# Schematic.net
KiCad netlist of a schematic drawn in Altium Designer
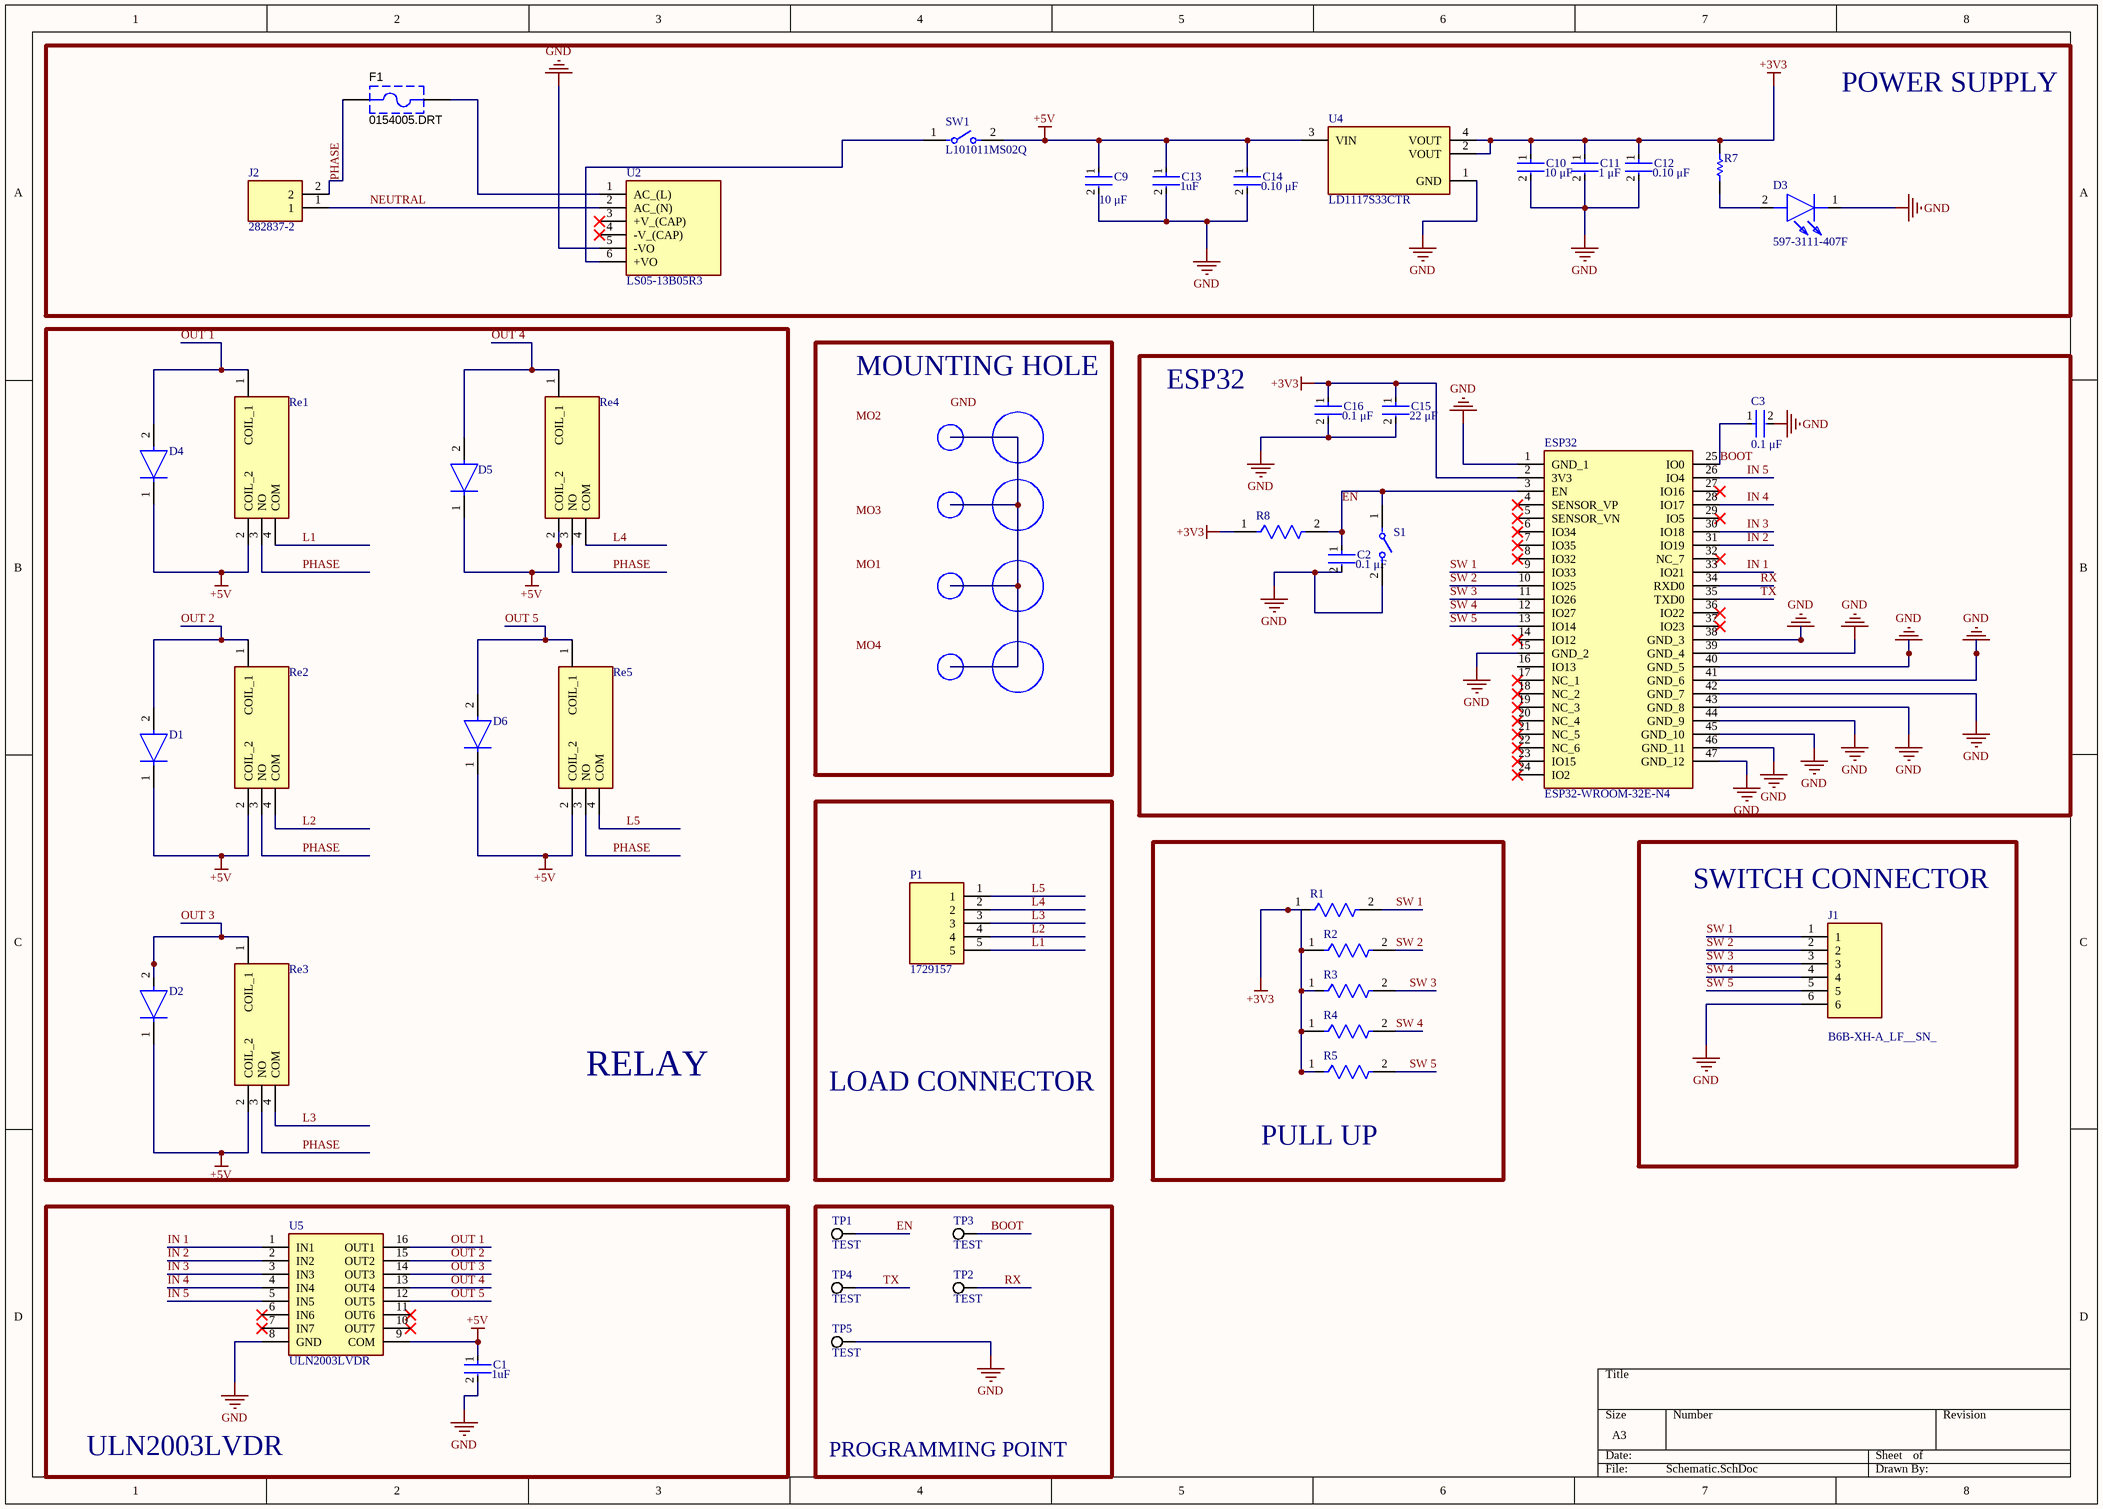
[diagram p0: Schematic.SchDoc]

(export (version "E")
  (design (tool "Eeschema 10.0.6"))
  (components
    (comp (ref "C1")
      (value "C0402C104K8PACTU")
      (footprint "FP-C0402-BB-MFG")
      (description "CAP CER 0.1UF 10V X5R 0402")
      (fields
        (field (name "CAPACITANCE") "1uF")
        (field (name "MANUFACTURER") "Kemet")
        (field (name "TOLERANCE") "0.1")
      )
      (libsource (lib "Altium Content Vault") (part "b4654b650e69147ec39a6b967a45e02"))
    )
    (comp (ref "C2")
      (value "0.1 μF")
      (footprint "FP-C0402-BB-MFG")
      (description "CAP CER 0.1UF 10V X5R 0402")
      (fields (field (name "MANUFACTURER") "Kemet") (field (name "TOLERANCE") "0.1"))
      (libsource (lib "Altium Content Vault") (part "b4654b650e69147ec39a6b967a45e02"))
    )
    (comp (ref "C3")
      (value "0.1 μF")
      (footprint "FP-C0402-BB-MFG")
      (description "CAP CER 0.1UF 10V X5R 0402")
      (fields (field (name "MANUFACTURER") "Kemet") (field (name "TOLERANCE") "0.1"))
      (libsource (lib "Altium Content Vault") (part "b4654b650e69147ec39a6b967a45e02"))
    )
    (comp (ref "C9")
      (value "10 μF")
      (footprint "FP-C0402-BB-MFG")
      (description "CAP CER 0.1UF 10V X5R 0402")
      (fields (field (name "MANUFACTURER") "Kemet") (field (name "TOLERANCE") "0.1"))
      (libsource (lib "Altium Content Vault") (part "b4654b650e69147ec39a6b967a45e02"))
    )
    (comp (ref "C10")
      (value "10 μF")
      (footprint "FP-C0402-BB-MFG")
      (description "CAP CER 0.1UF 10V X5R 0402")
      (fields (field (name "MANUFACTURER") "Kemet") (field (name "TOLERANCE") "0.1"))
      (libsource (lib "Altium Content Vault") (part "b4654b650e69147ec39a6b967a45e02"))
    )
    (comp (ref "C11")
      (value "1 μF")
      (footprint "FP-C0402-BB-MFG")
      (description "CAP CER 0.1UF 10V X5R 0402")
      (fields (field (name "MANUFACTURER") "Kemet") (field (name "TOLERANCE") "0.1"))
      (libsource (lib "Altium Content Vault") (part "b4654b650e69147ec39a6b967a45e02"))
    )
    (comp (ref "C12")
      (value "C0402C104K8PACTU")
      (footprint "FP-C0402-BB-MFG")
      (description "CAP CER 0.1UF 10V X5R 0402")
      (fields
        (field (name "CAPACITANCE") "0.10 μF")
        (field (name "MANUFACTURER") "Kemet")
        (field (name "TOLERANCE") "0.1")
      )
      (libsource (lib "Altium Content Vault") (part "b4654b650e69147ec39a6b967a45e02"))
    )
    (comp (ref "C13")
      (value "C0402C104K8PACTU")
      (footprint "FP-C0402-BB-MFG")
      (description "CAP CER 0.1UF 10V X5R 0402")
      (fields
        (field (name "CAPACITANCE") "1uF")
        (field (name "MANUFACTURER") "Kemet")
        (field (name "TOLERANCE") "0.1")
      )
      (libsource (lib "Altium Content Vault") (part "b4654b650e69147ec39a6b967a45e02"))
    )
    (comp (ref "C14")
      (value "0.10 μF")
      (footprint "FP-C0402-BB-MFG")
      (description "CAP CER 0.1UF 10V X5R 0402")
      (fields (field (name "MANUFACTURER") "Kemet") (field (name "TOLERANCE") "0.1"))
      (libsource (lib "Altium Content Vault") (part "b4654b650e69147ec39a6b967a45e02"))
    )
    (comp (ref "C15")
      (value "22 μF")
      (footprint "FP-C0402-BB-MFG")
      (description "CAP CER 0.1UF 10V X5R 0402")
      (fields (field (name "MANUFACTURER") "Kemet") (field (name "TOLERANCE") "0.1"))
      (libsource (lib "Altium Content Vault") (part "b4654b650e69147ec39a6b967a45e02"))
    )
    (comp (ref "C16")
      (value "0.1 μF")
      (footprint "FP-C0402-BB-MFG")
      (description "CAP CER 0.1UF 10V X5R 0402")
      (fields (field (name "MANUFACTURER") "Kemet") (field (name "TOLERANCE") "0.1"))
      (libsource (lib "Altium Content Vault") (part "b4654b650e69147ec39a6b967a45e02"))
    )
    (comp (ref "D1")
      (value "1N4148")
      (footprint "FP-017AG-MFG")
      (description "DIODE GEN PURP 100V 200MA DO35")
      (fields (field (name "VOLTAGE") "100V"))
      (libsource (lib "Altium Content Vault") (part "d7152d700b627762746794eb795d46e"))
    )
    (comp (ref "D2")
      (value "1N4148")
      (footprint "FP-017AG-MFG")
      (description "DIODE GEN PURP 100V 200MA DO35")
      (fields (field (name "VOLTAGE") "100V"))
      (libsource (lib "Altium Content Vault") (part "d7152d700b627762746794eb795d46e"))
    )
    (comp (ref "D3")
      (value "597-3111-407F")
      (footprint "SamacSys:LEDC3015X150N")
      (description "LED")
      (fields (field (name "MOUSER PART NUMBER") "645-597-3111-407F"))
      (libsource (lib "*") (part "597-3111-407F"))
    )
    (comp (ref "D4")
      (value "1N4148")
      (footprint "FP-017AG-MFG")
      (description "DIODE GEN PURP 100V 200MA DO35")
      (fields (field (name "VOLTAGE") "100V"))
      (libsource (lib "Altium Content Vault") (part "d7152d700b627762746794eb795d46e"))
    )
    (comp (ref "D5")
      (value "1N4148")
      (footprint "FP-017AG-MFG")
      (description "DIODE GEN PURP 100V 200MA DO35")
      (fields (field (name "VOLTAGE") "100V"))
      (libsource (lib "Altium Content Vault") (part "d7152d700b627762746794eb795d46e"))
    )
    (comp (ref "D6")
      (value "1N4148")
      (footprint "FP-017AG-MFG")
      (description "DIODE GEN PURP 100V 200MA DO35")
      (fields (field (name "VOLTAGE") "100V"))
      (libsource (lib "Altium Content Vault") (part "d7152d700b627762746794eb795d46e"))
    )
    (comp (ref "ESP32")
      (value "ESP32-WROOM-32E-N4")
      (footprint "SamacSys:ESP32WROOM32EN4")
      (description "Integrated Circuit")
      (fields (field (name "MOUSER PART NUMBER") "356-ESP32WRM32E132PH"))
      (libsource (lib "*") (part "ESP32-WROOM-32E-N4"))
    )
    (comp (ref "F1")
      (value "0154005.DRT")
      (footprint "LFUS-154_V")
      (description "Fuse and Holder Combination, 125 V, 5 A, -55 to 125 degC, 2-Pin SMD, RoHS, Tape and Reel")
      (fields (field (name "MANUFACTURER") "Littelfuse"))
      (libsource (lib "Altium Content Vault") (part "FUSE_HOLDER-2"))
    )
    (comp (ref "J1")
      (value "B6B-XH-A_LF__SN_")
      (footprint "SamacSys:SHDR6W64P0X250_1X6_1740X575X700P")
      (description "Connector")
      (fields
        (field (name "MANUFACTURER_PART_NUMBER") "B6B-XH-A(LF)(SN)")
        (field (name "MOUSER PART NUMBER") "306-B6BXHALFSN")
      )
      (libsource (lib "*") (part "B6B-XH-A_LF__SN_"))
    )
    (comp (ref "J2")
      (value "282837-2")
      (footprint "SamacSys:2828372")
      (description "Connector")
      (fields (field (name "MOUSER PART NUMBER") "571-2828372"))
      (libsource (lib "*") (part "282837-2"))
    )
    (comp (ref "P1")
      (value "1729157")
      (footprint "SamacSys:1729157")
      (description "Connector")
      (fields (field (name "MOUSER PART NUMBER") "651-1729157"))
      (libsource (lib "*") (part "1729157"))
    )
    (comp (ref "R1")
      (value "CRCW040210K0JNED")
      (footprint "FP-CRCW0402-e3-IPC_B")
      (description "RES Thick Film, 10kΩ, 5%, 0.063W, 200ppm/°C, 0402")
      (fields (field (name "TOLERANCE") "5%"))
      (libsource (lib "Altium Content Vault") (part "1029c3af85768c4190bb7ad29bc67b5"))
    )
    (comp (ref "R2")
      (value "CRCW040210K0JNED")
      (footprint "FP-CRCW0402-e3-IPC_B")
      (description "RES Thick Film, 10kΩ, 5%, 0.063W, 200ppm/°C, 0402")
      (fields (field (name "TOLERANCE") "5%"))
      (libsource (lib "Altium Content Vault") (part "1029c3af85768c4190bb7ad29bc67b5"))
    )
    (comp (ref "R3")
      (value "CRCW040210K0JNED")
      (footprint "FP-CRCW0402-e3-IPC_B")
      (description "RES Thick Film, 10kΩ, 5%, 0.063W, 200ppm/°C, 0402")
      (fields (field (name "TOLERANCE") "5%"))
      (libsource (lib "Altium Content Vault") (part "1029c3af85768c4190bb7ad29bc67b5"))
    )
    (comp (ref "R4")
      (value "CRCW040210K0JNED")
      (footprint "FP-CRCW0402-e3-IPC_B")
      (description "RES Thick Film, 10kΩ, 5%, 0.063W, 200ppm/°C, 0402")
      (fields (field (name "TOLERANCE") "5%"))
      (libsource (lib "Altium Content Vault") (part "1029c3af85768c4190bb7ad29bc67b5"))
    )
    (comp (ref "R5")
      (value "CRCW040210K0JNED")
      (footprint "FP-CRCW0402-e3-IPC_B")
      (description "RES Thick Film, 10kΩ, 5%, 0.063W, 200ppm/°C, 0402")
      (fields (field (name "TOLERANCE") "5%"))
      (libsource (lib "Altium Content Vault") (part "1029c3af85768c4190bb7ad29bc67b5"))
    )
    (comp (ref "R7")
      (value "ERJ-3EKF3300V")
      (footprint "RESC1608X55X30LL15T15")
      (description "Chip Resistor, 330 Ohm, +/- 1%, 0.1 W, -55 to 155 degC, 0603 (1608 Metric), RoHS, Tape and Reel")
      (libsource (lib "Altium Content Vault") (part "RES-2"))
    )
    (comp (ref "R8")
      (value "CRCW040210K0JNED")
      (footprint "FP-CRCW0402-e3-IPC_B")
      (description "RES Thick Film, 10kΩ, 5%, 0.063W, 200ppm/°C, 0402")
      (fields (field (name "TOLERANCE") "5%"))
      (libsource (lib "Altium Content Vault") (part "1029c3af85768c4190bb7ad29bc67b5"))
    )
    (comp (ref "Re1")
      (value "HF46F-G_5-HS1T")
      (footprint "SamacSys:HF46FG5HS1T")
      (description "Relay or Contactor")
      (fields (field (name "MANUFACTURER_PART_NUMBER") "HF46F-G/5-HS1T"))
      (libsource (lib "*") (part "HF46F-G_5-HS1T"))
    )
    (comp (ref "Re2")
      (value "HF46F-G_5-HS1T")
      (footprint "SamacSys:HF46FG5HS1T")
      (description "Relay or Contactor")
      (fields (field (name "MANUFACTURER_PART_NUMBER") "HF46F-G/5-HS1T"))
      (libsource (lib "*") (part "HF46F-G_5-HS1T"))
    )
    (comp (ref "Re3")
      (value "HF46F-G_5-HS1T")
      (footprint "SamacSys:HF46FG5HS1T")
      (description "Relay or Contactor")
      (fields (field (name "MANUFACTURER_PART_NUMBER") "HF46F-G/5-HS1T"))
      (libsource (lib "*") (part "HF46F-G_5-HS1T"))
    )
    (comp (ref "Re4")
      (value "HF46F-G_5-HS1T")
      (footprint "SamacSys:HF46FG5HS1T")
      (description "Relay or Contactor")
      (fields (field (name "MANUFACTURER_PART_NUMBER") "HF46F-G/5-HS1T"))
      (libsource (lib "*") (part "HF46F-G_5-HS1T"))
    )
    (comp (ref "Re5")
      (value "HF46F-G_5-HS1T")
      (footprint "SamacSys:HF46FG5HS1T")
      (description "Relay or Contactor")
      (fields (field (name "MANUFACTURER_PART_NUMBER") "HF46F-G/5-HS1T"))
      (libsource (lib "*") (part "HF46F-G_5-HS1T"))
    )
    (comp (ref "S1")
      (value "L101011MS02Q")
      (footprint "FP-L101011MS02Q-MFG")
      (description "SWITCH SLIDE SPST 4A 125V")
      (libsource (lib "Altium Content Vault") (part "bb27bde45df87f1f469753f287ef5ae"))
    )
    (comp (ref "SW1")
      (value "L101011MS02Q")
      (footprint "FP-L101011MS02Q-MFG")
      (description "SWITCH SLIDE SPST 4A 125V")
      (libsource (lib "Altium Content Vault") (part "bb27bde45df87f1f469753f287ef5ae"))
    )
    (comp (ref "TP1")
      (value "TEST")
      (footprint "KSTN-5012_V")
      (description "Test Point, White, Through Hole, RoHS, Bulk")
      (fields (field (name "MANUFACTURER") "Keystone"))
      (libsource (lib "Altium Content Vault") (part "TESTPOINT_WHITE"))
    )
    (comp (ref "TP2")
      (value "TEST")
      (footprint "KSTN-5012_V")
      (description "Test Point, White, Through Hole, RoHS, Bulk")
      (fields (field (name "MANUFACTURER") "Keystone"))
      (libsource (lib "Altium Content Vault") (part "TESTPOINT_WHITE"))
    )
    (comp (ref "TP3")
      (value "TEST")
      (footprint "KSTN-5012_V")
      (description "Test Point, White, Through Hole, RoHS, Bulk")
      (fields (field (name "MANUFACTURER") "Keystone"))
      (libsource (lib "Altium Content Vault") (part "TESTPOINT_WHITE"))
    )
    (comp (ref "TP4")
      (value "TEST")
      (footprint "KSTN-5012_V")
      (description "Test Point, White, Through Hole, RoHS, Bulk")
      (fields (field (name "MANUFACTURER") "Keystone"))
      (libsource (lib "Altium Content Vault") (part "TESTPOINT_WHITE"))
    )
    (comp (ref "TP5")
      (value "TEST")
      (footprint "KSTN-5012_V")
      (description "Test Point, White, Through Hole, RoHS, Bulk")
      (fields (field (name "MANUFACTURER") "Keystone"))
      (libsource (lib "Altium Content Vault") (part "TESTPOINT_WHITE"))
    )
    (comp (ref "U2")
      (value "LS05-13B05R3")
      (footprint "SamacSys:LS0513B05R3")
      (description "Power Supply")
      (libsource (lib "*") (part "LS05-13B05R3"))
    )
    (comp (ref "U4")
      (value "LD1117S33CTR")
      (footprint "FP-SOT-223-0046067_14-MFG")
      (description "IC REG LINEAR 3.3V 800MA SOT223")
      (libsource (lib "Altium Content Vault") (part "7818869c5c16ceab15634627166a29d"))
    )
    (comp (ref "U5")
      (value "ULN2003LVDR")
      (footprint "SamacSys:SOIC127P600X175-16N")
      (description "Integrated Circuit")
      (fields (field (name "MOUSER PART NUMBER") "595-ULN2003LVDR"))
      (libsource (lib "*") (part "ULN2003LVDR"))
    )
  )
  (nets
    (net (code "1") (name "+3V3") (class "Default")
      (node (ref "C10") (pin "1") (pinfunction "1_1") (pintype "passive"))
      (node (ref "C11") (pin "1") (pinfunction "1_1") (pintype "passive"))
      (node (ref "C12") (pin "1") (pinfunction "1_1") (pintype "passive"))
      (node (ref "C15") (pin "1") (pinfunction "1_1") (pintype "passive"))
      (node (ref "C16") (pin "1") (pinfunction "1_1") (pintype "passive"))
      (node (ref "ESP32") (pin "2") (pinfunction "3V3_2") (pintype "passive"))
      (node (ref "R1") (pin "1") (pinfunction "1_1") (pintype "passive"))
      (node (ref "R2") (pin "1") (pinfunction "1_1") (pintype "passive"))
      (node (ref "R3") (pin "1") (pinfunction "1_1") (pintype "passive"))
      (node (ref "R4") (pin "1") (pinfunction "1_1") (pintype "passive"))
      (node (ref "R5") (pin "1") (pinfunction "1_1") (pintype "passive"))
      (node (ref "R7") (pin "2") (pinfunction "2_2") (pintype "passive"))
      (node (ref "R8") (pin "1") (pinfunction "1_1") (pintype "passive"))
      (node (ref "U4") (pin "2") (pinfunction "VOUT_2") (pintype "power_in"))
      (node (ref "U4") (pin "4") (pinfunction "VOUT_4") (pintype "power_in"))
    )
    (net (code "2") (name "+5V") (class "Default")
      (node (ref "C1") (pin "1") (pinfunction "1_1") (pintype "passive"))
      (node (ref "C13") (pin "1") (pinfunction "1_1") (pintype "passive"))
      (node (ref "C14") (pin "1") (pinfunction "1_1") (pintype "passive"))
      (node (ref "C9") (pin "1") (pinfunction "1_1") (pintype "passive"))
      (node (ref "D1") (pin "1") (pinfunction "C_1") (pintype "passive"))
      (node (ref "D2") (pin "1") (pinfunction "C_1") (pintype "passive"))
      (node (ref "D4") (pin "1") (pinfunction "C_1") (pintype "passive"))
      (node (ref "D5") (pin "1") (pinfunction "C_1") (pintype "passive"))
      (node (ref "D6") (pin "1") (pinfunction "C_1") (pintype "passive"))
      (node (ref "Re1") (pin "2") (pinfunction "COIL_2_2") (pintype "passive"))
      (node (ref "Re2") (pin "2") (pinfunction "COIL_2_2") (pintype "passive"))
      (node (ref "Re3") (pin "2") (pinfunction "COIL_2_2") (pintype "passive"))
      (node (ref "Re4") (pin "2") (pinfunction "COIL_2_2") (pintype "passive"))
      (node (ref "Re5") (pin "2") (pinfunction "COIL_2_2") (pintype "passive"))
      (node (ref "SW1") (pin "2") (pinfunction "2_2") (pintype "passive"))
      (node (ref "U4") (pin "3") (pinfunction "VIN_3") (pintype "power_in"))
      (node (ref "U5") (pin "9") (pinfunction "COM_9") (pintype "passive"))
    )
    (net (code "3") (name "/BOOT") (class "Default")
      (node (ref "C3") (pin "1") (pinfunction "1_1") (pintype "passive"))
      (node (ref "ESP32") (pin "25") (pinfunction "IO0_25") (pintype "passive"))
      (node (ref "TP3") (pin "1") (pinfunction "1_1") (pintype "passive"))
    )
    (net (code "4") (name "/EN") (class "Default")
      (node (ref "C2") (pin "1") (pinfunction "1_1") (pintype "passive"))
      (node (ref "ESP32") (pin "3") (pinfunction "EN_3") (pintype "passive"))
      (node (ref "R8") (pin "2") (pinfunction "2_2") (pintype "passive"))
      (node (ref "S1") (pin "1") (pinfunction "1_1") (pintype "passive"))
      (node (ref "TP1") (pin "1") (pinfunction "1_1") (pintype "passive"))
    )
    (net (code "5") (name "/IN 1") (class "Default")
      (node (ref "ESP32") (pin "33") (pinfunction "IO21_33") (pintype "passive"))
      (node (ref "U5") (pin "1") (pinfunction "IN1_1") (pintype "passive"))
    )
    (net (code "6") (name "/IN 2") (class "Default")
      (node (ref "ESP32") (pin "31") (pinfunction "IO19_31") (pintype "passive"))
      (node (ref "U5") (pin "2") (pinfunction "IN2_2") (pintype "passive"))
    )
    (net (code "7") (name "/IN 3") (class "Default")
      (node (ref "ESP32") (pin "30") (pinfunction "IO18_30") (pintype "passive"))
      (node (ref "U5") (pin "3") (pinfunction "IN3_3") (pintype "passive"))
    )
    (net (code "8") (name "/IN 4") (class "Default")
      (node (ref "ESP32") (pin "28") (pinfunction "IO17_28") (pintype "passive"))
      (node (ref "U5") (pin "4") (pinfunction "IN4_4") (pintype "passive"))
    )
    (net (code "9") (name "/IN 5") (class "Default")
      (node (ref "ESP32") (pin "26") (pinfunction "IO4_26") (pintype "passive"))
      (node (ref "U5") (pin "5") (pinfunction "IN5_5") (pintype "passive"))
    )
    (net (code "10") (name "/L1") (class "Default")
      (node (ref "P1") (pin "5") (pinfunction "5_5") (pintype "passive"))
      (node (ref "Re1") (pin "4") (pinfunction "COM_4") (pintype "passive"))
    )
    (net (code "11") (name "/L2") (class "Default")
      (node (ref "P1") (pin "4") (pinfunction "4_4") (pintype "passive"))
      (node (ref "Re2") (pin "4") (pinfunction "COM_4") (pintype "passive"))
    )
    (net (code "12") (name "/L3") (class "Default")
      (node (ref "P1") (pin "3") (pinfunction "3_3") (pintype "passive"))
      (node (ref "Re3") (pin "4") (pinfunction "COM_4") (pintype "passive"))
    )
    (net (code "13") (name "/L4") (class "Default")
      (node (ref "P1") (pin "2") (pinfunction "2_2") (pintype "passive"))
      (node (ref "Re4") (pin "4") (pinfunction "COM_4") (pintype "passive"))
    )
    (net (code "14") (name "/L5") (class "Default")
      (node (ref "P1") (pin "1") (pinfunction "1_1") (pintype "passive"))
      (node (ref "Re5") (pin "4") (pinfunction "COM_4") (pintype "passive"))
    )
    (net (code "19") (name "/NEUTRAL") (class "Default")
      (node (ref "J2") (pin "1") (pinfunction "1_1") (pintype "passive"))
      (node (ref "U2") (pin "2") (pinfunction "AC_(N)_2") (pintype "passive"))
    )
    (net (code "20") (name "/OUT 1") (class "Default")
      (node (ref "D4") (pin "2") (pinfunction "A_2") (pintype "passive"))
      (node (ref "Re1") (pin "1") (pinfunction "COIL_1_1") (pintype "passive"))
      (node (ref "U5") (pin "16") (pinfunction "OUT1_16") (pintype "passive"))
    )
    (net (code "21") (name "/OUT 2") (class "Default")
      (node (ref "D1") (pin "2") (pinfunction "A_2") (pintype "passive"))
      (node (ref "Re2") (pin "1") (pinfunction "COIL_1_1") (pintype "passive"))
      (node (ref "U5") (pin "15") (pinfunction "OUT2_15") (pintype "passive"))
    )
    (net (code "22") (name "/OUT 3") (class "Default")
      (node (ref "D2") (pin "2") (pinfunction "A_2") (pintype "passive"))
      (node (ref "Re3") (pin "1") (pinfunction "COIL_1_1") (pintype "passive"))
      (node (ref "U5") (pin "14") (pinfunction "OUT3_14") (pintype "passive"))
    )
    (net (code "23") (name "/OUT 4") (class "Default")
      (node (ref "D5") (pin "2") (pinfunction "A_2") (pintype "passive"))
      (node (ref "Re4") (pin "1") (pinfunction "COIL_1_1") (pintype "passive"))
      (node (ref "U5") (pin "13") (pinfunction "OUT4_13") (pintype "passive"))
    )
    (net (code "24") (name "/OUT 5") (class "Default")
      (node (ref "D6") (pin "2") (pinfunction "A_2") (pintype "passive"))
      (node (ref "Re5") (pin "1") (pinfunction "COIL_1_1") (pintype "passive"))
      (node (ref "U5") (pin "12") (pinfunction "OUT5_12") (pintype "passive"))
    )
    (net (code "25") (name "/PHASE") (class "Default")
      (node (ref "F1") (pin "1") (pinfunction "1_1") (pintype "passive"))
      (node (ref "J2") (pin "2") (pinfunction "2_2") (pintype "passive"))
      (node (ref "Re1") (pin "3") (pinfunction "NO_3") (pintype "passive"))
      (node (ref "Re2") (pin "3") (pinfunction "NO_3") (pintype "passive"))
      (node (ref "Re3") (pin "3") (pinfunction "NO_3") (pintype "passive"))
      (node (ref "Re4") (pin "3") (pinfunction "NO_3") (pintype "passive"))
      (node (ref "Re5") (pin "3") (pinfunction "NO_3") (pintype "passive"))
    )
    (net (code "26") (name "/RX") (class "Default")
      (node (ref "ESP32") (pin "34") (pinfunction "RXD0_34") (pintype "passive"))
      (node (ref "TP2") (pin "1") (pinfunction "1_1") (pintype "passive"))
    )
    (net (code "27") (name "/SW 1") (class "Default")
      (node (ref "ESP32") (pin "9") (pinfunction "IO33_9") (pintype "passive"))
      (node (ref "J1") (pin "1") (pinfunction "1_1") (pintype "passive"))
      (node (ref "R1") (pin "2") (pinfunction "2_2") (pintype "passive"))
    )
    (net (code "28") (name "/SW 2") (class "Default")
      (node (ref "ESP32") (pin "10") (pinfunction "IO25_10") (pintype "passive"))
      (node (ref "J1") (pin "2") (pinfunction "2_2") (pintype "passive"))
      (node (ref "R2") (pin "2") (pinfunction "2_2") (pintype "passive"))
    )
    (net (code "29") (name "/SW 3") (class "Default")
      (node (ref "ESP32") (pin "11") (pinfunction "IO26_11") (pintype "passive"))
      (node (ref "J1") (pin "3") (pinfunction "3_3") (pintype "passive"))
      (node (ref "R3") (pin "2") (pinfunction "2_2") (pintype "passive"))
    )
    (net (code "30") (name "/SW 4") (class "Default")
      (node (ref "ESP32") (pin "12") (pinfunction "IO27_12") (pintype "passive"))
      (node (ref "J1") (pin "4") (pinfunction "4_4") (pintype "passive"))
      (node (ref "R4") (pin "2") (pinfunction "2_2") (pintype "passive"))
    )
    (net (code "31") (name "/SW 5") (class "Default")
      (node (ref "ESP32") (pin "13") (pinfunction "IO14_13") (pintype "passive"))
      (node (ref "J1") (pin "5") (pinfunction "5_5") (pintype "passive"))
      (node (ref "R5") (pin "2") (pinfunction "2_2") (pintype "passive"))
    )
    (net (code "32") (name "/TX") (class "Default")
      (node (ref "ESP32") (pin "35") (pinfunction "TXD0_35") (pintype "passive"))
      (node (ref "TP4") (pin "1") (pinfunction "1_1") (pintype "passive"))
    )
    (net (code "33") (name "GND") (class "Default")
      (node (ref "C1") (pin "2") (pinfunction "2_2") (pintype "passive"))
      (node (ref "C10") (pin "2") (pinfunction "2_2") (pintype "passive"))
      (node (ref "C11") (pin "2") (pinfunction "2_2") (pintype "passive"))
      (node (ref "C12") (pin "2") (pinfunction "2_2") (pintype "passive"))
      (node (ref "C13") (pin "2") (pinfunction "2_2") (pintype "passive"))
      (node (ref "C14") (pin "2") (pinfunction "2_2") (pintype "passive"))
      (node (ref "C15") (pin "2") (pinfunction "2_2") (pintype "passive"))
      (node (ref "C16") (pin "2") (pinfunction "2_2") (pintype "passive"))
      (node (ref "C2") (pin "2") (pinfunction "2_2") (pintype "passive"))
      (node (ref "C3") (pin "2") (pinfunction "2_2") (pintype "passive"))
      (node (ref "C9") (pin "2") (pinfunction "2_2") (pintype "passive"))
      (node (ref "D3") (pin "1") (pinfunction "K_1") (pintype "passive"))
      (node (ref "ESP32") (pin "1") (pinfunction "GND_1_1") (pintype "passive"))
      (node (ref "ESP32") (pin "15") (pinfunction "GND_2_15") (pintype "passive"))
      (node (ref "ESP32") (pin "38") (pinfunction "GND_3_38") (pintype "passive"))
      (node (ref "ESP32") (pin "39") (pinfunction "GND_4_39") (pintype "passive"))
      (node (ref "ESP32") (pin "40") (pinfunction "GND_5_40") (pintype "passive"))
      (node (ref "ESP32") (pin "41") (pinfunction "GND_6_41") (pintype "passive"))
      (node (ref "ESP32") (pin "42") (pinfunction "GND_7_42") (pintype "passive"))
      (node (ref "ESP32") (pin "43") (pinfunction "GND_8_43") (pintype "passive"))
      (node (ref "ESP32") (pin "44") (pinfunction "GND_9_44") (pintype "passive"))
      (node (ref "ESP32") (pin "45") (pinfunction "GND_10_45") (pintype "passive"))
      (node (ref "ESP32") (pin "46") (pinfunction "GND_11_46") (pintype "passive"))
      (node (ref "ESP32") (pin "47") (pinfunction "GND_12_47") (pintype "passive"))
      (node (ref "J1") (pin "6") (pinfunction "6_6") (pintype "passive"))
      (node (ref "S1") (pin "2") (pinfunction "2_2") (pintype "passive"))
      (node (ref "TP5") (pin "1") (pinfunction "1_1") (pintype "passive"))
      (node (ref "U2") (pin "5") (pinfunction "-VO_5") (pintype "passive"))
      (node (ref "U4") (pin "1") (pinfunction "GND_1") (pintype "power_in"))
      (node (ref "U5") (pin "8") (pinfunction "GND_8") (pintype "passive"))
    )
    (net (code "34") (name "Net-(D3-A)") (class "Default")
      (node (ref "D3") (pin "2") (pinfunction "A_2") (pintype "passive"))
      (node (ref "R7") (pin "1") (pinfunction "1_1") (pintype "passive"))
    )
    (net (code "35") (name "Net-(U2-+VO)") (class "Default")
      (node (ref "SW1") (pin "1") (pinfunction "1_1") (pintype "passive"))
      (node (ref "U2") (pin "6") (pinfunction "+VO_6") (pintype "passive"))
    )
    (net (code "36") (name "Net-(U2-AC_(L))") (class "Default")
      (node (ref "F1") (pin "2") (pinfunction "2_2") (pintype "passive"))
      (node (ref "U2") (pin "1") (pinfunction "AC_(L)_1") (pintype "passive"))
    )
    (net (code "37") (name "unconnected-(ESP32-IO2-Pad24)") (class "Default")
      (node (ref "ESP32") (pin "24") (pinfunction "IO2_24") (pintype "passive+no_connect"))
    )
    (net (code "38") (name "unconnected-(ESP32-IO5-Pad29)") (class "Default")
      (node (ref "ESP32") (pin "29") (pinfunction "IO5_29") (pintype "passive+no_connect"))
    )
    (net (code "39") (name "unconnected-(ESP32-IO12-Pad14)") (class "Default")
      (node (ref "ESP32") (pin "14") (pinfunction "IO12_14") (pintype "passive+no_connect"))
    )
    (net (code "40") (name "unconnected-(ESP32-IO13-Pad16)") (class "Default")
      (node (ref "ESP32") (pin "16") (pinfunction "IO13_16") (pintype "passive"))
    )
    (net (code "41") (name "unconnected-(ESP32-IO15-Pad23)") (class "Default")
      (node (ref "ESP32") (pin "23") (pinfunction "IO15_23") (pintype "passive+no_connect"))
    )
    (net (code "42") (name "unconnected-(ESP32-IO16-Pad27)") (class "Default")
      (node (ref "ESP32") (pin "27") (pinfunction "IO16_27") (pintype "passive+no_connect"))
    )
    (net (code "43") (name "unconnected-(ESP32-IO22-Pad36)") (class "Default")
      (node (ref "ESP32") (pin "36") (pinfunction "IO22_36") (pintype "passive+no_connect"))
    )
    (net (code "44") (name "unconnected-(ESP32-IO23-Pad37)") (class "Default")
      (node (ref "ESP32") (pin "37") (pinfunction "IO23_37") (pintype "passive+no_connect"))
    )
    (net (code "45") (name "unconnected-(ESP32-IO32-Pad8)") (class "Default")
      (node (ref "ESP32") (pin "8") (pinfunction "IO32_8") (pintype "passive+no_connect"))
    )
    (net (code "46") (name "unconnected-(ESP32-IO34-Pad6)") (class "Default")
      (node (ref "ESP32") (pin "6") (pinfunction "IO34_6") (pintype "passive+no_connect"))
    )
    (net (code "47") (name "unconnected-(ESP32-IO35-Pad7)") (class "Default")
      (node (ref "ESP32") (pin "7") (pinfunction "IO35_7") (pintype "passive+no_connect"))
    )
    (net (code "48") (name "unconnected-(ESP32-NC_1-Pad17)") (class "Default")
      (node (ref "ESP32") (pin "17") (pinfunction "NC_1_17") (pintype "passive+no_connect"))
    )
    (net (code "49") (name "unconnected-(ESP32-NC_2-Pad18)") (class "Default")
      (node (ref "ESP32") (pin "18") (pinfunction "NC_2_18") (pintype "passive+no_connect"))
    )
    (net (code "50") (name "unconnected-(ESP32-NC_3-Pad19)") (class "Default")
      (node (ref "ESP32") (pin "19") (pinfunction "NC_3_19") (pintype "passive+no_connect"))
    )
    (net (code "51") (name "unconnected-(ESP32-NC_4-Pad20)") (class "Default")
      (node (ref "ESP32") (pin "20") (pinfunction "NC_4_20") (pintype "passive+no_connect"))
    )
    (net (code "52") (name "unconnected-(ESP32-NC_5-Pad21)") (class "Default")
      (node (ref "ESP32") (pin "21") (pinfunction "NC_5_21") (pintype "passive+no_connect"))
    )
    (net (code "53") (name "unconnected-(ESP32-NC_6-Pad22)") (class "Default")
      (node (ref "ESP32") (pin "22") (pinfunction "NC_6_22") (pintype "passive+no_connect"))
    )
    (net (code "54") (name "unconnected-(ESP32-NC_7-Pad32)") (class "Default")
      (node (ref "ESP32") (pin "32") (pinfunction "NC_7_32") (pintype "passive+no_connect"))
    )
    (net (code "55") (name "unconnected-(ESP32-SENSOR_VN-Pad5)") (class "Default")
      (node (ref "ESP32") (pin "5") (pinfunction "SENSOR_VN_5") (pintype "passive+no_connect"))
    )
    (net (code "56") (name "unconnected-(ESP32-SENSOR_VP-Pad4)") (class "Default")
      (node (ref "ESP32") (pin "4") (pinfunction "SENSOR_VP_4") (pintype "passive+no_connect"))
    )
    (net (code "57") (name "unconnected-(U2-+V_(CAP)-Pad3)") (class "Default")
      (node (ref "U2") (pin "3") (pinfunction "+V_(CAP)_3") (pintype "passive+no_connect"))
    )
    (net (code "58") (name "unconnected-(U2--V_(CAP)-Pad4)") (class "Default")
      (node (ref "U2") (pin "4") (pinfunction "-V_(CAP)_4") (pintype "passive+no_connect"))
    )
    (net (code "59") (name "unconnected-(U5-IN6-Pad6)") (class "Default")
      (node (ref "U5") (pin "6") (pinfunction "IN6_6") (pintype "passive+no_connect"))
    )
    (net (code "60") (name "unconnected-(U5-IN7-Pad7)") (class "Default")
      (node (ref "U5") (pin "7") (pinfunction "IN7_7") (pintype "passive+no_connect"))
    )
    (net (code "61") (name "unconnected-(U5-OUT6-Pad11)") (class "Default")
      (node (ref "U5") (pin "11") (pinfunction "OUT6_11") (pintype "passive+no_connect"))
    )
    (net (code "62") (name "unconnected-(U5-OUT7-Pad10)") (class "Default")
      (node (ref "U5") (pin "10") (pinfunction "OUT7_10") (pintype "passive+no_connect"))
    )
  )
)
